# mds.net
KiCad netlist of a schematic drawn in EAGLE
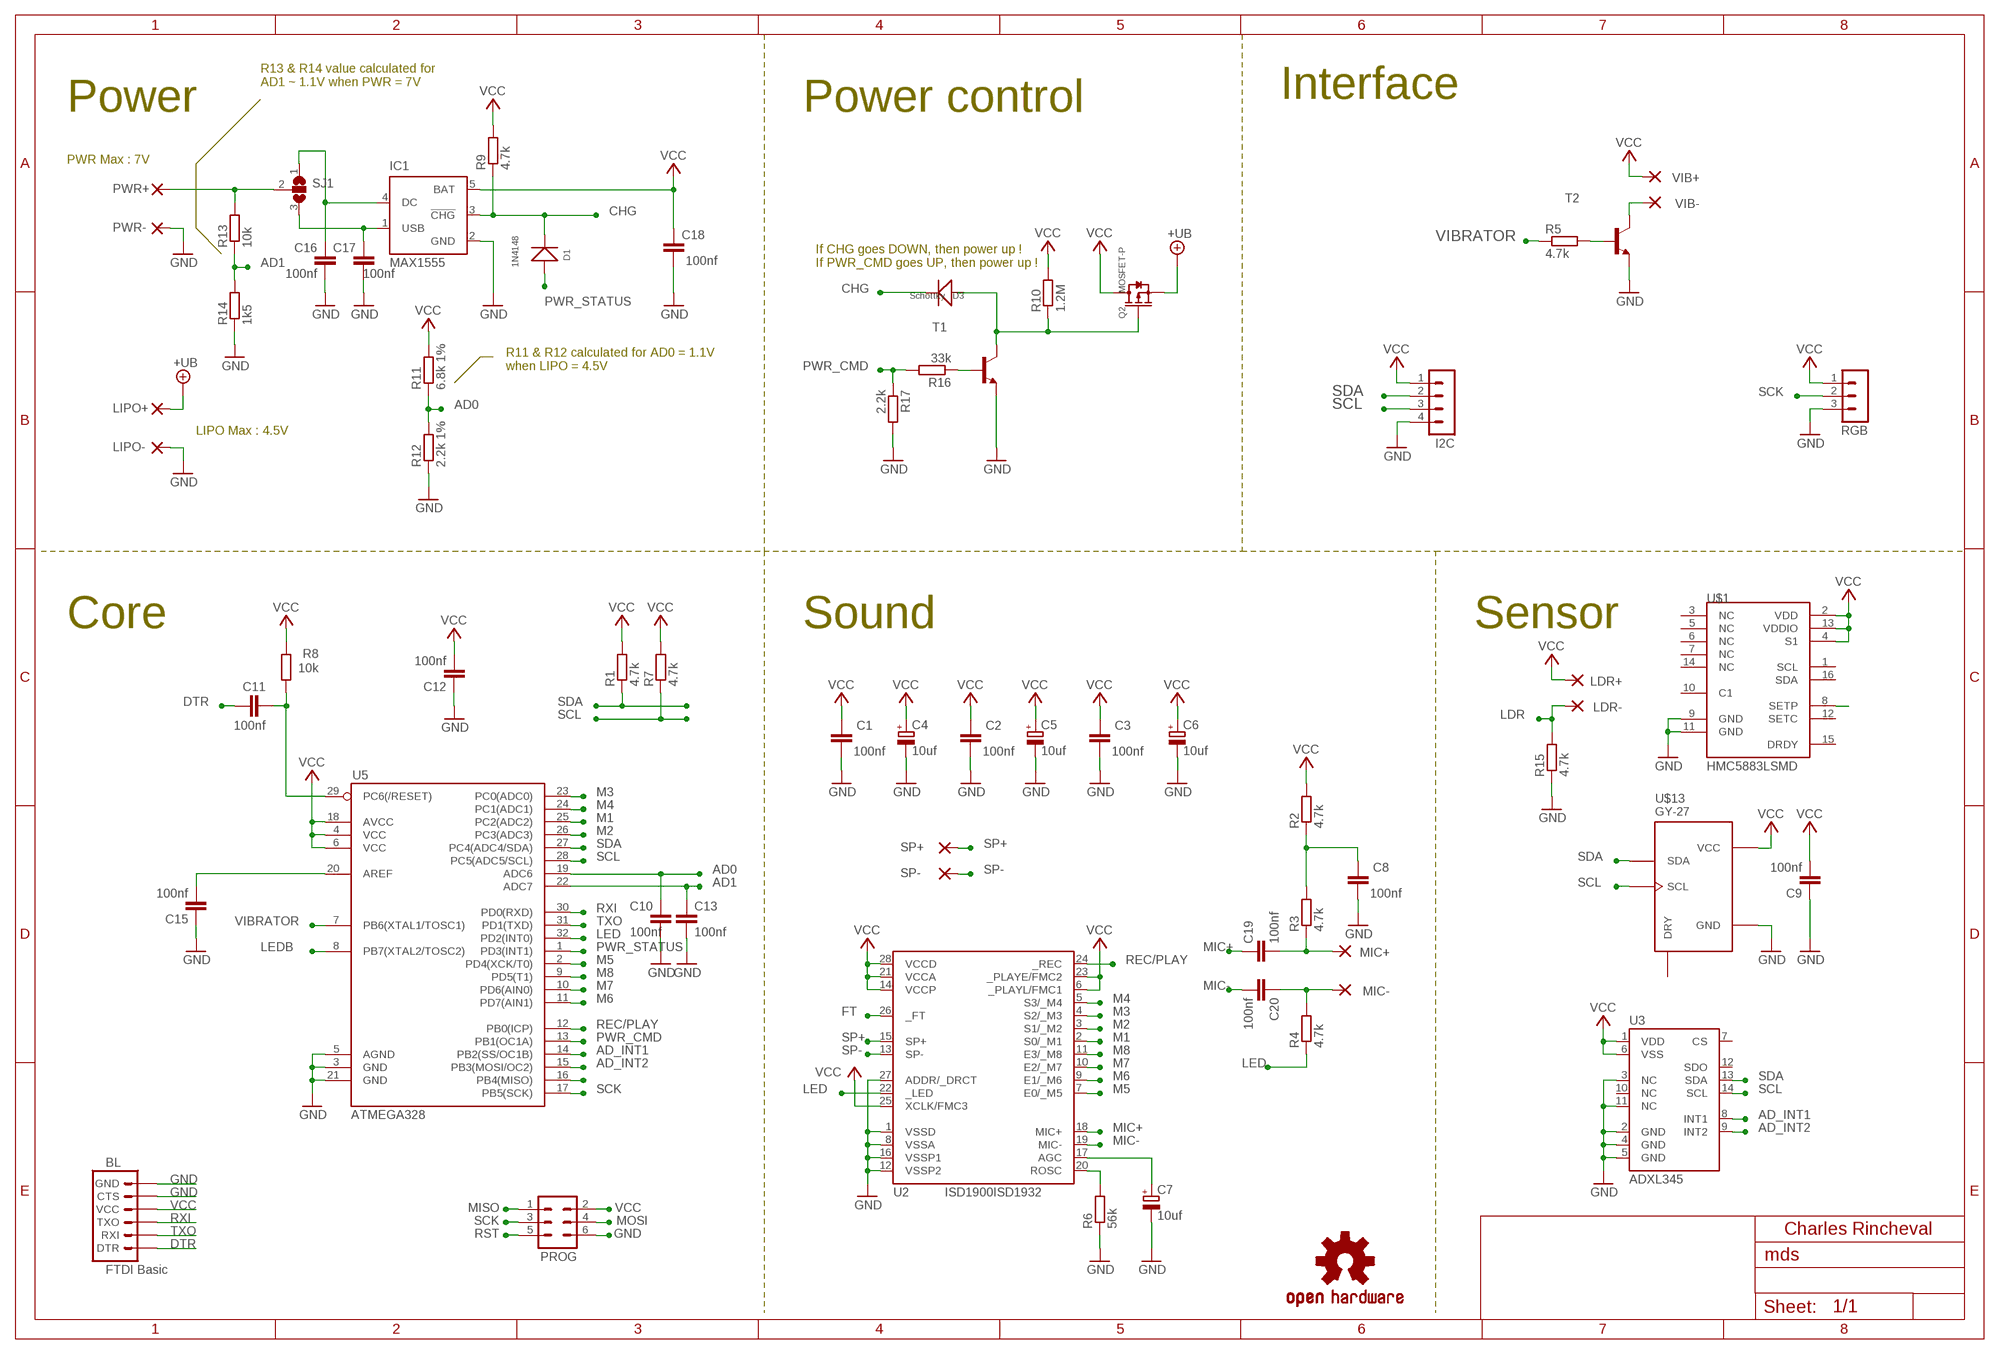
[diagram p0: schematic, sheet 1]

(export (version "E")
  (design (tool "Eeschema 10.0.6"))
  (components
    (comp (ref "BL")
      (value "FTDI Basic")
      (footprint "eagle-import:1X06")
      (libsource (lib "eagle-import") (part "ARDUINO_SERIAL_PROGRAMPTH"))
    )
    (comp (ref "C1")
      (value "100nf")
      (footprint "eagle-import:C0805")
      (libsource (lib "eagle-import") (part "C-EUC0805"))
    )
    (comp (ref "C2")
      (value "100nf")
      (footprint "eagle-import:C0805")
      (libsource (lib "eagle-import") (part "C-EUC0805"))
    )
    (comp (ref "C3")
      (value "100nf")
      (footprint "eagle-import:C0805")
      (libsource (lib "eagle-import") (part "C-EUC0805"))
    )
    (comp (ref "C4")
      (value "10uf")
      (footprint "eagle-import:CT3528")
      (libsource (lib "eagle-import") (part "CPOL-EUCT3528"))
    )
    (comp (ref "C5")
      (value "10uf")
      (footprint "eagle-import:CT3528")
      (libsource (lib "eagle-import") (part "CPOL-EUCT3528"))
    )
    (comp (ref "C6")
      (value "10uf")
      (footprint "eagle-import:CT3528")
      (libsource (lib "eagle-import") (part "CPOL-EUCT3528"))
    )
    (comp (ref "C7")
      (value "10uf")
      (footprint "eagle-import:CT3528")
      (libsource (lib "eagle-import") (part "CPOL-EUCT3528"))
    )
    (comp (ref "C8")
      (value "100nf")
      (footprint "eagle-import:C0805")
      (libsource (lib "eagle-import") (part "C-EUC0805"))
    )
    (comp (ref "C9")
      (value "100nf")
      (footprint "eagle-import:C0805")
      (libsource (lib "eagle-import") (part "C-EUC0805"))
    )
    (comp (ref "C10")
      (value "100nf")
      (footprint "eagle-import:C0805")
      (libsource (lib "eagle-import") (part "C-EUC0805"))
    )
    (comp (ref "C11")
      (value "100nf")
      (footprint "eagle-import:C0805")
      (libsource (lib "eagle-import") (part "C-EUC0805"))
    )
    (comp (ref "C12")
      (value "100nf")
      (footprint "eagle-import:C0805")
      (libsource (lib "eagle-import") (part "C-EUC0805"))
    )
    (comp (ref "C13")
      (value "100nf")
      (footprint "eagle-import:C0805")
      (libsource (lib "eagle-import") (part "C-EUC0805"))
    )
    (comp (ref "C15")
      (value "100nf")
      (footprint "eagle-import:C0805")
      (libsource (lib "eagle-import") (part "C-EUC0805"))
    )
    (comp (ref "C16")
      (value "100nf")
      (footprint "eagle-import:C0805")
      (libsource (lib "eagle-import") (part "C-EUC0805"))
    )
    (comp (ref "C17")
      (value "100nf")
      (footprint "eagle-import:C0805")
      (libsource (lib "eagle-import") (part "C-EUC0805"))
    )
    (comp (ref "C18")
      (value "100nf")
      (footprint "eagle-import:C0805")
      (libsource (lib "eagle-import") (part "C-EUC0805"))
    )
    (comp (ref "C19")
      (value "100nf")
      (footprint "eagle-import:C0805")
      (libsource (lib "eagle-import") (part "C-EUC0805"))
    )
    (comp (ref "C20")
      (value "100nf")
      (footprint "eagle-import:C0805")
      (libsource (lib "eagle-import") (part "C-EUC0805"))
    )
    (comp (ref "D1")
      (value "1N4148")
      (footprint "eagle-import:LL-34")
      (libsource (lib "eagle-import") (part "D-D1206"))
    )
    (comp (ref "D3")
      (value "Schottky")
      (footprint "eagle-import:LL-34")
      (libsource (lib "eagle-import") (part "D-D1206"))
    )
    (comp (ref "I2C")
      (value "MA04-1")
      (footprint "eagle-import:MA04-1")
      (libsource (lib "eagle-import") (part "MA04-1"))
    )
    (comp (ref "IC1")
      (value "MAX1555")
      (footprint "eagle-import:SOT23-5L")
      (fields (field (name "MF") "MAXIM") (field (name "MPN") "MAX1555EZK+T"))
      (libsource (lib "eagle-import") (part "MAX1555"))
    )
    (comp (ref "LDR+")
      (value "1,6/0,8")
      (footprint "eagle-import:1,6_0,8")
      (libsource (lib "eagle-import") (part "1,6/0,8"))
    )
    (comp (ref "LDR-")
      (value "1,6/0,8")
      (footprint "eagle-import:1,6_0,8")
      (libsource (lib "eagle-import") (part "1,6/0,8"))
    )
    (comp (ref "LIPO+")
      (value "1,6/0,8")
      (footprint "eagle-import:1,6_0,8")
      (libsource (lib "eagle-import") (part "1,6/0,8"))
    )
    (comp (ref "LIPO-")
      (value "1,6/0,8")
      (footprint "eagle-import:1,6_0,8")
      (libsource (lib "eagle-import") (part "1,6/0,8"))
    )
    (comp (ref "MIC+")
      (value "1,6/0,8")
      (footprint "eagle-import:1,6_0,8")
      (libsource (lib "eagle-import") (part "1,6/0,8"))
    )
    (comp (ref "MIC-")
      (value "1,6/0,8")
      (footprint "eagle-import:1,6_0,8")
      (libsource (lib "eagle-import") (part "1,6/0,8"))
    )
    (comp (ref "PROG")
      (value "MA03-2")
      (footprint "eagle-import:MA03-2")
      (libsource (lib "eagle-import") (part "MA03-2"))
    )
    (comp (ref "PWR+")
      (value "1,6/0,8")
      (footprint "eagle-import:1,6_0,8")
      (libsource (lib "eagle-import") (part "1,6/0,8"))
    )
    (comp (ref "PWR-")
      (value "1,6/0,8")
      (footprint "eagle-import:1,6_0,8")
      (libsource (lib "eagle-import") (part "1,6/0,8"))
    )
    (comp (ref "Q2")
      (value "MOSFET-P")
      (footprint "eagle-import:SOT23")
      (libsource (lib "eagle-import") (part "MOSFET-P-044021001"))
    )
    (comp (ref "R1")
      (value "4.7k")
      (footprint "eagle-import:M0805")
      (libsource (lib "eagle-import") (part "R-EU_M0805"))
    )
    (comp (ref "R2")
      (value "4.7k")
      (footprint "eagle-import:M0805")
      (libsource (lib "eagle-import") (part "R-EU_M0805"))
    )
    (comp (ref "R3")
      (value "4.7k")
      (footprint "eagle-import:M0805")
      (libsource (lib "eagle-import") (part "R-EU_M0805"))
    )
    (comp (ref "R4")
      (value "4.7k")
      (footprint "eagle-import:M0805")
      (libsource (lib "eagle-import") (part "R-EU_M0805"))
    )
    (comp (ref "R5")
      (value "4.7k")
      (footprint "eagle-import:M0805")
      (libsource (lib "eagle-import") (part "R-EU_M0805"))
    )
    (comp (ref "R6")
      (value "56k")
      (footprint "eagle-import:M0805")
      (libsource (lib "eagle-import") (part "R-EU_M0805"))
    )
    (comp (ref "R7")
      (value "4.7k")
      (footprint "eagle-import:M0805")
      (libsource (lib "eagle-import") (part "R-EU_M0805"))
    )
    (comp (ref "R8")
      (value "10k")
      (footprint "eagle-import:M0805")
      (libsource (lib "eagle-import") (part "R-EU_M0805"))
    )
    (comp (ref "R9")
      (value "4.7k")
      (footprint "eagle-import:M0805")
      (libsource (lib "eagle-import") (part "R-EU_M0805"))
    )
    (comp (ref "R10")
      (value "1.2M")
      (footprint "eagle-import:M0805")
      (libsource (lib "eagle-import") (part "R-EU_M0805"))
    )
    (comp (ref "R11")
      (value "6.8k 1%")
      (footprint "eagle-import:M0805")
      (libsource (lib "eagle-import") (part "R-EU_M0805"))
    )
    (comp (ref "R12")
      (value "2.2k 1%")
      (footprint "eagle-import:M0805")
      (libsource (lib "eagle-import") (part "R-EU_M0805"))
    )
    (comp (ref "R13")
      (value "10k")
      (footprint "eagle-import:M0805")
      (libsource (lib "eagle-import") (part "R-EU_M0805"))
    )
    (comp (ref "R14")
      (value "1k5")
      (footprint "eagle-import:M0805")
      (libsource (lib "eagle-import") (part "R-EU_M0805"))
    )
    (comp (ref "R15")
      (value "4.7k")
      (footprint "eagle-import:M0805")
      (libsource (lib "eagle-import") (part "R-EU_M0805"))
    )
    (comp (ref "R16")
      (value "33k")
      (footprint "eagle-import:M0805")
      (libsource (lib "eagle-import") (part "R-EU_M0805"))
    )
    (comp (ref "R17")
      (value "2.2k")
      (footprint "eagle-import:M0805")
      (libsource (lib "eagle-import") (part "R-EU_M0805"))
    )
    (comp (ref "RGB")
      (value "MA03-1")
      (footprint "eagle-import:MA03-1")
      (libsource (lib "eagle-import") (part "MA03-1"))
    )
    (comp (ref "SJ1")
      (value "SJ2W")
      (footprint "eagle-import:SJ_2")
      (libsource (lib "eagle-import") (part "SJ2W"))
    )
    (comp (ref "SP+")
      (value "1,6/0,8")
      (footprint "eagle-import:1,6_0,8")
      (libsource (lib "eagle-import") (part "1,6/0,8"))
    )
    (comp (ref "SP-")
      (value "1,6/0,8")
      (footprint "eagle-import:1,6_0,8")
      (libsource (lib "eagle-import") (part "1,6/0,8"))
    )
    (comp (ref "T1")
      (value "MMBT2222ALT1-NPN-SOT23-BEC")
      (footprint "eagle-import:SOT23-BEC")
      (libsource (lib "eagle-import") (part "-NPN-SOT23-BECMMBT2222ALT1"))
    )
    (comp (ref "T2")
      (value "MMBT2222ALT1-NPN-SOT23-BEC")
      (footprint "eagle-import:SOT23-BEC")
      (libsource (lib "eagle-import") (part "-NPN-SOT23-BECMMBT2222ALT1"))
    )
    (comp (ref "U$1")
      (value "HMC5883LSMD")
      (footprint "eagle-import:16LPCC")
      (libsource (lib "eagle-import") (part "HMC5883LSMD"))
    )
    (comp (ref "U$13")
      (value "GY-27")
      (footprint "eagle-import:GY-27")
      (libsource (lib "eagle-import") (part "GY-27"))
    )
    (comp (ref "U$14")
      (value "OSHW-LOGOS")
      (footprint "eagle-import:OSHW-LOGO-S")
      (libsource (lib "eagle-import") (part "OSHW-LOGOS"))
    )
    (comp (ref "U2")
      (value "ISD1900ISD1932")
      (footprint "eagle-import:SO-28W")
      (libsource (lib "eagle-import") (part "ISD1900ISD1932"))
    )
    (comp (ref "U3")
      (value "ADXL345")
      (footprint "eagle-import:LGA14")
      (libsource (lib "eagle-import") (part "ADXL345"))
    )
    (comp (ref "U5")
      (value "ATMEGA328")
      (footprint "eagle-import:TQFP32-08")
      (libsource (lib "eagle-import") (part "ATMEGA168"))
    )
    (comp (ref "VIB+")
      (value "1,6/0,8")
      (footprint "eagle-import:1,6_0,8")
      (libsource (lib "eagle-import") (part "1,6/0,8"))
    )
    (comp (ref "VIB-")
      (value "1,6/0,8")
      (footprint "eagle-import:1,6_0,8")
      (libsource (lib "eagle-import") (part "1,6/0,8"))
    )
  )
  (nets
    (net (code "1") (name "+UB") (class "Default")
      (node (ref "LIPO+") (pin "1") (pinfunction "P_1") (pintype "passive"))
      (node (ref "Q2") (pin "2") (pinfunction "S_2") (pintype "passive"))
    )
    (net (code "2") (name "/AD0") (class "Default")
      (node (ref "C10") (pin "1") (pinfunction "1_1") (pintype "passive"))
      (node (ref "R11") (pin "1") (pinfunction "1_1") (pintype "passive"))
      (node (ref "R12") (pin "2") (pinfunction "2_2") (pintype "passive"))
      (node (ref "U5") (pin "19") (pinfunction "ADC6_19") (pintype "bidirectional"))
    )
    (net (code "3") (name "/AD1") (class "Default")
      (node (ref "C13") (pin "1") (pinfunction "1_1") (pintype "passive"))
      (node (ref "R13") (pin "1") (pinfunction "1_1") (pintype "passive"))
      (node (ref "R14") (pin "2") (pinfunction "2_2") (pintype "passive"))
      (node (ref "U5") (pin "22") (pinfunction "ADC7_22") (pintype "bidirectional"))
    )
    (net (code "4") (name "/AD_INT1") (class "Default")
      (node (ref "U3") (pin "8") (pinfunction "INT1_8") (pintype "bidirectional"))
      (node (ref "U5") (pin "14") (pinfunction "PB2(SS/OC1B)_14") (pintype "bidirectional"))
    )
    (net (code "5") (name "/AD_INT2") (class "Default")
      (node (ref "U3") (pin "9") (pinfunction "INT2_9") (pintype "bidirectional"))
      (node (ref "U5") (pin "15") (pinfunction "PB3(MOSI/OC2)_15") (pintype "bidirectional"))
    )
    (net (code "6") (name "/CHG") (class "Default")
      (node (ref "D1") (pin "C") (pinfunction "-_C") (pintype "passive"))
      (node (ref "D3") (pin "C") (pinfunction "-_C") (pintype "passive"))
      (node (ref "IC1") (pin "3") (pinfunction "~{CHG}_3") (pintype "output"))
      (node (ref "R9") (pin "1") (pinfunction "1_1") (pintype "passive"))
    )
    (net (code "7") (name "/DTR") (class "Default")
      (node (ref "BL") (pin "1") (pinfunction "DTR_1") (pintype "passive"))
      (node (ref "C11") (pin "1") (pinfunction "1_1") (pintype "passive"))
    )
    (net (code "8") (name "/FT") (class "Default")
      (node (ref "U2") (pin "26") (pinfunction "_FT_26") (pintype "bidirectional"))
    )
    (net (code "9") (name "/LDR") (class "Default")
      (node (ref "LDR-") (pin "1") (pinfunction "P_1") (pintype "passive"))
      (node (ref "R15") (pin "2") (pinfunction "2_2") (pintype "passive"))
    )
    (net (code "10") (name "/LED") (class "Default")
      (node (ref "R4") (pin "1") (pinfunction "1_1") (pintype "passive"))
      (node (ref "U2") (pin "22") (pinfunction "_LED_22") (pintype "bidirectional"))
      (node (ref "U5") (pin "32") (pinfunction "PD2(INT0)_32") (pintype "bidirectional"))
    )
    (net (code "11") (name "/LEDB") (class "Default")
      (node (ref "U5") (pin "8") (pinfunction "PB7(XTAL2/TOSC2)_8") (pintype "bidirectional"))
    )
    (net (code "12") (name "/M1") (class "Default")
      (node (ref "U2") (pin "2") (pinfunction "S0/_M1_2") (pintype "bidirectional"))
      (node (ref "U5") (pin "25") (pinfunction "PC2(ADC2)_25") (pintype "bidirectional"))
    )
    (net (code "13") (name "/M2") (class "Default")
      (node (ref "U2") (pin "3") (pinfunction "S1/_M2_3") (pintype "bidirectional"))
      (node (ref "U5") (pin "26") (pinfunction "PC3(ADC3)_26") (pintype "bidirectional"))
    )
    (net (code "14") (name "/M3") (class "Default")
      (node (ref "U2") (pin "4") (pinfunction "S2/_M3_4") (pintype "bidirectional"))
      (node (ref "U5") (pin "23") (pinfunction "PC0(ADC0)_23") (pintype "bidirectional"))
    )
    (net (code "15") (name "/M4") (class "Default")
      (node (ref "U2") (pin "5") (pinfunction "S3/_M4_5") (pintype "bidirectional"))
      (node (ref "U5") (pin "24") (pinfunction "PC1(ADC1)_24") (pintype "bidirectional"))
    )
    (net (code "16") (name "/M5") (class "Default")
      (node (ref "U2") (pin "7") (pinfunction "E0/_M5_7") (pintype "bidirectional"))
      (node (ref "U5") (pin "2") (pinfunction "PD4(XCK/T0)_2") (pintype "bidirectional"))
    )
    (net (code "17") (name "/M6") (class "Default")
      (node (ref "U2") (pin "9") (pinfunction "E1/_M6_9") (pintype "bidirectional"))
      (node (ref "U5") (pin "11") (pinfunction "PD7(AIN1)_11") (pintype "bidirectional"))
    )
    (net (code "18") (name "/M7") (class "Default")
      (node (ref "U2") (pin "10") (pinfunction "E2/_M7_10") (pintype "bidirectional"))
      (node (ref "U5") (pin "10") (pinfunction "PD6(AIN0)_10") (pintype "bidirectional"))
    )
    (net (code "19") (name "/M8") (class "Default")
      (node (ref "U2") (pin "11") (pinfunction "E3/_M8_11") (pintype "bidirectional"))
      (node (ref "U5") (pin "9") (pinfunction "PD5(T1)_9") (pintype "bidirectional"))
    )
    (net (code "20") (name "/MIC+") (class "Default")
      (node (ref "C19") (pin "1") (pinfunction "1_1") (pintype "passive"))
      (node (ref "U2") (pin "18") (pinfunction "MIC+_18") (pintype "bidirectional"))
    )
    (net (code "21") (name "/MIC-") (class "Default")
      (node (ref "C20") (pin "2") (pinfunction "2_2") (pintype "passive"))
      (node (ref "U2") (pin "19") (pinfunction "MIC-_19") (pintype "bidirectional"))
    )
    (net (code "22") (name "/MISO") (class "Default")
      (node (ref "PROG") (pin "1") (pinfunction "1_1") (pintype "passive"))
    )
    (net (code "23") (name "/MOSI") (class "Default")
      (node (ref "PROG") (pin "4") (pinfunction "4_4") (pintype "passive"))
    )
    (net (code "24") (name "/PWR_CMD") (class "Default")
      (node (ref "R16") (pin "2") (pinfunction "2_2") (pintype "passive"))
      (node (ref "R17") (pin "1") (pinfunction "1_1") (pintype "passive"))
      (node (ref "U5") (pin "13") (pinfunction "PB1(OC1A)_13") (pintype "bidirectional"))
    )
    (net (code "25") (name "/PWR_STATUS") (class "Default")
      (node (ref "D1") (pin "A") (pinfunction "+_A") (pintype "passive"))
      (node (ref "U5") (pin "1") (pinfunction "PD3(INT1)_1") (pintype "bidirectional"))
    )
    (net (code "26") (name "/REC{slash}PLAY") (class "Default")
      (node (ref "U2") (pin "24") (pinfunction "_REC_24") (pintype "bidirectional"))
      (node (ref "U5") (pin "12") (pinfunction "PB0(ICP)_12") (pintype "bidirectional"))
    )
    (net (code "27") (name "/RST") (class "Default")
      (node (ref "C11") (pin "2") (pinfunction "2_2") (pintype "passive"))
      (node (ref "PROG") (pin "5") (pinfunction "5_5") (pintype "passive"))
      (node (ref "R8") (pin "1") (pinfunction "1_1") (pintype "passive"))
      (node (ref "U5") (pin "29") (pinfunction "PC6(/RESET)_29") (pintype "bidirectional"))
    )
    (net (code "28") (name "/RXI") (class "Default")
      (node (ref "BL") (pin "3") (pinfunction "TXO_3") (pintype "passive"))
      (node (ref "U5") (pin "30") (pinfunction "PD0(RXD)_30") (pintype "bidirectional"))
    )
    (net (code "29") (name "/SCK") (class "Default")
      (node (ref "PROG") (pin "3") (pinfunction "3_3") (pintype "passive"))
      (node (ref "RGB") (pin "2") (pinfunction "2_2") (pintype "passive"))
      (node (ref "U5") (pin "17") (pinfunction "PB5(SCK)_17") (pintype "bidirectional"))
    )
    (net (code "30") (name "/SCL") (class "Default")
      (node (ref "I2C") (pin "3") (pinfunction "3_3") (pintype "passive"))
      (node (ref "R7") (pin "1") (pinfunction "1_1") (pintype "passive"))
      (node (ref "U$13") (pin "SCL") (pinfunction "SCL_SCL") (pintype "input"))
      (node (ref "U3") (pin "14") (pinfunction "SCL_14") (pintype "bidirectional"))
      (node (ref "U5") (pin "28") (pinfunction "PC5(ADC5/SCL)_28") (pintype "bidirectional"))
    )
    (net (code "31") (name "/SDA") (class "Default")
      (node (ref "I2C") (pin "2") (pinfunction "2_2") (pintype "passive"))
      (node (ref "R1") (pin "1") (pinfunction "1_1") (pintype "passive"))
      (node (ref "U$13") (pin "SDA") (pinfunction "SDA_SDA") (pintype "bidirectional"))
      (node (ref "U3") (pin "13") (pinfunction "SDA_13") (pintype "bidirectional"))
      (node (ref "U5") (pin "27") (pinfunction "PC4(ADC4/SDA)_27") (pintype "bidirectional"))
    )
    (net (code "32") (name "/SP+") (class "Default")
      (node (ref "SP+") (pin "1") (pinfunction "P_1") (pintype "passive"))
      (node (ref "U2") (pin "15") (pinfunction "SP+_15") (pintype "bidirectional"))
    )
    (net (code "33") (name "/SP-") (class "Default")
      (node (ref "SP-") (pin "1") (pinfunction "P_1") (pintype "passive"))
      (node (ref "U2") (pin "13") (pinfunction "SP-_13") (pintype "bidirectional"))
    )
    (net (code "34") (name "/TXO") (class "Default")
      (node (ref "BL") (pin "2") (pinfunction "RXI_2") (pintype "passive"))
      (node (ref "U5") (pin "31") (pinfunction "PD1(TXD)_31") (pintype "bidirectional"))
    )
    (net (code "35") (name "/VIBRATOR") (class "Default")
      (node (ref "R5") (pin "1") (pinfunction "1_1") (pintype "passive"))
      (node (ref "U5") (pin "7") (pinfunction "PB6(XTAL1/TOSC1)_7") (pintype "bidirectional"))
    )
    (net (code "36") (name "GND") (class "Default")
      (node (ref "BL") (pin "5") (pinfunction "CTS_5") (pintype "passive"))
      (node (ref "BL") (pin "6") (pinfunction "GND_6") (pintype "passive"))
      (node (ref "C1") (pin "1") (pinfunction "1_1") (pintype "passive"))
      (node (ref "C10") (pin "2") (pinfunction "2_2") (pintype "passive"))
      (node (ref "C12") (pin "1") (pinfunction "1_1") (pintype "passive"))
      (node (ref "C13") (pin "2") (pinfunction "2_2") (pintype "passive"))
      (node (ref "C15") (pin "1") (pinfunction "1_1") (pintype "passive"))
      (node (ref "C16") (pin "1") (pinfunction "1_1") (pintype "passive"))
      (node (ref "C17") (pin "1") (pinfunction "1_1") (pintype "passive"))
      (node (ref "C18") (pin "1") (pinfunction "1_1") (pintype "passive"))
      (node (ref "C2") (pin "1") (pinfunction "1_1") (pintype "passive"))
      (node (ref "C3") (pin "1") (pinfunction "1_1") (pintype "passive"))
      (node (ref "C4") (pin "-") (pinfunction "-_-") (pintype "passive"))
      (node (ref "C5") (pin "-") (pinfunction "-_-") (pintype "passive"))
      (node (ref "C6") (pin "-") (pinfunction "-_-") (pintype "passive"))
      (node (ref "C7") (pin "-") (pinfunction "-_-") (pintype "passive"))
      (node (ref "C8") (pin "1") (pinfunction "1_1") (pintype "passive"))
      (node (ref "C9") (pin "1") (pinfunction "1_1") (pintype "passive"))
      (node (ref "I2C") (pin "4") (pinfunction "4_4") (pintype "passive"))
      (node (ref "IC1") (pin "2") (pinfunction "GND_2") (pintype "power_in"))
      (node (ref "LIPO-") (pin "1") (pinfunction "P_1") (pintype "passive"))
      (node (ref "PROG") (pin "6") (pinfunction "6_6") (pintype "passive"))
      (node (ref "PWR-") (pin "1") (pinfunction "P_1") (pintype "passive"))
      (node (ref "R12") (pin "1") (pinfunction "1_1") (pintype "passive"))
      (node (ref "R14") (pin "1") (pinfunction "1_1") (pintype "passive"))
      (node (ref "R15") (pin "1") (pinfunction "1_1") (pintype "passive"))
      (node (ref "R17") (pin "2") (pinfunction "2_2") (pintype "passive"))
      (node (ref "R6") (pin "1") (pinfunction "1_1") (pintype "passive"))
      (node (ref "RGB") (pin "3") (pinfunction "3_3") (pintype "passive"))
      (node (ref "T1") (pin "E") (pinfunction "E_E") (pintype "passive"))
      (node (ref "T2") (pin "E") (pinfunction "E_E") (pintype "passive"))
      (node (ref "U$1") (pin "11") (pinfunction "GND_11") (pintype "bidirectional"))
      (node (ref "U$1") (pin "9") (pinfunction "GND_9") (pintype "bidirectional"))
      (node (ref "U$13") (pin "GND") (pinfunction "GND_GND") (pintype "power_in"))
      (node (ref "U2") (pin "1") (pinfunction "VSSD_1") (pintype "bidirectional"))
      (node (ref "U2") (pin "12") (pinfunction "VSSP2_12") (pintype "bidirectional"))
      (node (ref "U2") (pin "16") (pinfunction "VSSP1_16") (pintype "bidirectional"))
      (node (ref "U2") (pin "27") (pinfunction "ADDR/_DRCT_27") (pintype "bidirectional"))
      (node (ref "U2") (pin "8") (pinfunction "VSSA_8") (pintype "bidirectional"))
      (node (ref "U3") (pin "11") (pinfunction "NC_11") (pintype "bidirectional"))
      (node (ref "U3") (pin "2") (pinfunction "GND_2") (pintype "bidirectional"))
      (node (ref "U3") (pin "3") (pinfunction "NC_3") (pintype "bidirectional"))
      (node (ref "U3") (pin "4") (pinfunction "GND_4") (pintype "bidirectional"))
      (node (ref "U3") (pin "5") (pinfunction "GND_5") (pintype "bidirectional"))
      (node (ref "U5") (pin "21") (pinfunction "GND_21") (pintype "bidirectional"))
      (node (ref "U5") (pin "3") (pinfunction "GND_3") (pintype "bidirectional"))
      (node (ref "U5") (pin "5") (pinfunction "AGND_5") (pintype "bidirectional"))
    )
    (net (code "37") (name "Net-(C8-Pad2)") (class "Default")
      (node (ref "C8") (pin "2") (pinfunction "2_2") (pintype "passive"))
      (node (ref "R2") (pin "1") (pinfunction "1_1") (pintype "passive"))
      (node (ref "R3") (pin "2") (pinfunction "2_2") (pintype "passive"))
    )
    (net (code "38") (name "Net-(IC1-DC)") (class "Default")
      (node (ref "C16") (pin "2") (pinfunction "2_2") (pintype "passive"))
      (node (ref "IC1") (pin "4") (pinfunction "DC_4") (pintype "input"))
      (node (ref "SJ1") (pin "1") (pinfunction "1_1") (pintype "passive"))
    )
    (net (code "39") (name "Net-(IC1-USB)") (class "Default")
      (node (ref "C17") (pin "2") (pinfunction "2_2") (pintype "passive"))
      (node (ref "IC1") (pin "1") (pinfunction "USB_1") (pintype "input"))
      (node (ref "SJ1") (pin "3") (pinfunction "3_3") (pintype "passive"))
    )
    (net (code "40") (name "Net-(MIC+-P)") (class "Default")
      (node (ref "C19") (pin "2") (pinfunction "2_2") (pintype "passive"))
      (node (ref "MIC+") (pin "1") (pinfunction "P_1") (pintype "passive"))
      (node (ref "R3") (pin "1") (pinfunction "1_1") (pintype "passive"))
    )
    (net (code "41") (name "Net-(MIC--P)") (class "Default")
      (node (ref "C20") (pin "1") (pinfunction "1_1") (pintype "passive"))
      (node (ref "MIC-") (pin "1") (pinfunction "P_1") (pintype "passive"))
      (node (ref "R4") (pin "2") (pinfunction "2_2") (pintype "passive"))
    )
    (net (code "42") (name "Net-(PWR+-P)") (class "Default")
      (node (ref "PWR+") (pin "1") (pinfunction "P_1") (pintype "passive"))
      (node (ref "R13") (pin "2") (pinfunction "2_2") (pintype "passive"))
      (node (ref "SJ1") (pin "2") (pinfunction "2_2") (pintype "passive"))
    )
    (net (code "43") (name "Net-(Q2-G)") (class "Default")
      (node (ref "Q2") (pin "1") (pinfunction "G_1") (pintype "passive"))
      (node (ref "R10") (pin "1") (pinfunction "1_1") (pintype "passive"))
      (node (ref "T1") (pin "C") (pinfunction "C_C") (pintype "passive"))
    )
    (net (code "44") (name "Net-(R5-Pad2)") (class "Default")
      (node (ref "R5") (pin "2") (pinfunction "2_2") (pintype "passive"))
      (node (ref "T2") (pin "B") (pinfunction "B_B") (pintype "passive"))
    )
    (net (code "45") (name "Net-(R16-Pad1)") (class "Default")
      (node (ref "R16") (pin "1") (pinfunction "1_1") (pintype "passive"))
      (node (ref "T1") (pin "B") (pinfunction "B_B") (pintype "passive"))
    )
    (net (code "46") (name "Net-(U2-AGC)") (class "Default")
      (node (ref "C7") (pin "+") (pinfunction "+_+") (pintype "passive"))
      (node (ref "U2") (pin "17") (pinfunction "AGC_17") (pintype "bidirectional"))
    )
    (net (code "47") (name "Net-(U2-ROSC)") (class "Default")
      (node (ref "R6") (pin "2") (pinfunction "2_2") (pintype "passive"))
      (node (ref "U2") (pin "20") (pinfunction "ROSC_20") (pintype "bidirectional"))
    )
    (net (code "48") (name "Net-(U5-AREF)") (class "Default")
      (node (ref "C15") (pin "2") (pinfunction "2_2") (pintype "passive"))
      (node (ref "U5") (pin "20") (pinfunction "AREF_20") (pintype "bidirectional"))
    )
    (net (code "49") (name "Net-(VIB--P)") (class "Default")
      (node (ref "T2") (pin "C") (pinfunction "C_C") (pintype "passive"))
      (node (ref "VIB-") (pin "1") (pinfunction "P_1") (pintype "passive"))
    )
    (net (code "50") (name "VCC") (class "Default")
      (node (ref "BL") (pin "4") (pinfunction "VCC_4") (pintype "passive"))
      (node (ref "C1") (pin "2") (pinfunction "2_2") (pintype "passive"))
      (node (ref "C12") (pin "2") (pinfunction "2_2") (pintype "passive"))
      (node (ref "C18") (pin "2") (pinfunction "2_2") (pintype "passive"))
      (node (ref "C2") (pin "2") (pinfunction "2_2") (pintype "passive"))
      (node (ref "C3") (pin "2") (pinfunction "2_2") (pintype "passive"))
      (node (ref "C4") (pin "+") (pinfunction "+_+") (pintype "passive"))
      (node (ref "C5") (pin "+") (pinfunction "+_+") (pintype "passive"))
      (node (ref "C6") (pin "+") (pinfunction "+_+") (pintype "passive"))
      (node (ref "C9") (pin "2") (pinfunction "2_2") (pintype "passive"))
      (node (ref "I2C") (pin "1") (pinfunction "1_1") (pintype "passive"))
      (node (ref "IC1") (pin "5") (pinfunction "BAT_5") (pintype "passive"))
      (node (ref "LDR+") (pin "1") (pinfunction "P_1") (pintype "passive"))
      (node (ref "PROG") (pin "2") (pinfunction "2_2") (pintype "passive"))
      (node (ref "Q2") (pin "3") (pinfunction "D_3") (pintype "passive"))
      (node (ref "R1") (pin "2") (pinfunction "2_2") (pintype "passive"))
      (node (ref "R10") (pin "2") (pinfunction "2_2") (pintype "passive"))
      (node (ref "R11") (pin "2") (pinfunction "2_2") (pintype "passive"))
      (node (ref "R2") (pin "2") (pinfunction "2_2") (pintype "passive"))
      (node (ref "R7") (pin "2") (pinfunction "2_2") (pintype "passive"))
      (node (ref "R8") (pin "2") (pinfunction "2_2") (pintype "passive"))
      (node (ref "R9") (pin "2") (pinfunction "2_2") (pintype "passive"))
      (node (ref "RGB") (pin "1") (pinfunction "1_1") (pintype "passive"))
      (node (ref "U$1") (pin "13") (pinfunction "VDDIO_13") (pintype "bidirectional"))
      (node (ref "U$1") (pin "2") (pinfunction "VDD_2") (pintype "bidirectional"))
      (node (ref "U$1") (pin "4") (pinfunction "S1_4") (pintype "bidirectional"))
      (node (ref "U$13") (pin "VCC") (pinfunction "VCC_VCC") (pintype "power_in"))
      (node (ref "U2") (pin "14") (pinfunction "VCCP_14") (pintype "bidirectional"))
      (node (ref "U2") (pin "21") (pinfunction "VCCA_21") (pintype "bidirectional"))
      (node (ref "U2") (pin "23") (pinfunction "_PLAYE/FMC2_23") (pintype "bidirectional"))
      (node (ref "U2") (pin "25") (pinfunction "XCLK/FMC3_25") (pintype "bidirectional"))
      (node (ref "U2") (pin "28") (pinfunction "VCCD_28") (pintype "bidirectional"))
      (node (ref "U2") (pin "6") (pinfunction "_PLAYL/FMC1_6") (pintype "bidirectional"))
      (node (ref "U3") (pin "1") (pinfunction "VDD_1") (pintype "bidirectional"))
      (node (ref "U3") (pin "6") (pinfunction "VSS_6") (pintype "bidirectional"))
      (node (ref "U5") (pin "18") (pinfunction "AVCC_18") (pintype "bidirectional"))
      (node (ref "U5") (pin "4") (pinfunction "VCC_4") (pintype "bidirectional"))
      (node (ref "U5") (pin "6") (pinfunction "VCC_6") (pintype "bidirectional"))
      (node (ref "VIB+") (pin "1") (pinfunction "P_1") (pintype "passive"))
    )
    (net (code "51") (name "unconnected-(D3-+-PadA)") (class "Default")
      (node (ref "D3") (pin "A") (pinfunction "+_A") (pintype "passive"))
    )
    (net (code "52") (name "unconnected-(U$1-C1-Pad10)") (class "Default")
      (node (ref "U$1") (pin "10") (pinfunction "C1_10") (pintype "bidirectional"))
    )
    (net (code "53") (name "unconnected-(U$1-DRDY-Pad15)") (class "Default")
      (node (ref "U$1") (pin "15") (pinfunction "DRDY_15") (pintype "bidirectional"))
    )
    (net (code "54") (name "unconnected-(U$1-NC-Pad3)") (class "Default")
      (node (ref "U$1") (pin "3") (pinfunction "NC_3") (pintype "bidirectional"))
    )
    (net (code "55") (name "unconnected-(U$1-NC-Pad5)") (class "Default")
      (node (ref "U$1") (pin "5") (pinfunction "NC_5") (pintype "bidirectional"))
    )
    (net (code "56") (name "unconnected-(U$1-NC-Pad6)") (class "Default")
      (node (ref "U$1") (pin "6") (pinfunction "NC_6") (pintype "bidirectional"))
    )
    (net (code "57") (name "unconnected-(U$1-NC-Pad7)") (class "Default")
      (node (ref "U$1") (pin "7") (pinfunction "NC_7") (pintype "bidirectional"))
    )
    (net (code "58") (name "unconnected-(U$1-NC-Pad14)") (class "Default")
      (node (ref "U$1") (pin "14") (pinfunction "NC_14") (pintype "bidirectional"))
    )
    (net (code "59") (name "unconnected-(U$1-SCL-Pad1)") (class "Default")
      (node (ref "U$1") (pin "1") (pinfunction "SCL_1") (pintype "bidirectional"))
    )
    (net (code "60") (name "unconnected-(U$1-SDA-Pad16)") (class "Default")
      (node (ref "U$1") (pin "16") (pinfunction "SDA_16") (pintype "bidirectional"))
    )
    (net (code "61") (name "unconnected-(U$1-SETC-Pad12)") (class "Default")
      (node (ref "U$1") (pin "12") (pinfunction "SETC_12") (pintype "bidirectional"))
    )
    (net (code "62") (name "unconnected-(U$1-SETP-Pad8)") (class "Default")
      (node (ref "U$1") (pin "8") (pinfunction "SETP_8") (pintype "bidirectional"))
    )
    (net (code "63") (name "unconnected-(U$13-PadDRY)") (class "Default")
      (node (ref "U$13") (pin "DRY") (pinfunction "DRY_DRY") (pintype "bidirectional"))
    )
    (net (code "64") (name "unconnected-(U3-CS-Pad7)") (class "Default")
      (node (ref "U3") (pin "7") (pinfunction "CS_7") (pintype "bidirectional"))
    )
    (net (code "65") (name "unconnected-(U3-NC-Pad10)") (class "Default")
      (node (ref "U3") (pin "10") (pinfunction "NC_10") (pintype "bidirectional"))
    )
    (net (code "66") (name "unconnected-(U3-SDO-Pad12)") (class "Default")
      (node (ref "U3") (pin "12") (pinfunction "SDO_12") (pintype "bidirectional"))
    )
    (net (code "67") (name "unconnected-(U5-PB4(MISO)-Pad16)") (class "Default")
      (node (ref "U5") (pin "16") (pinfunction "PB4(MISO)_16") (pintype "bidirectional"))
    )
  )
)
